# MOTOR_MAQUINA.net
KiCad netlist of a schematic drawn in Altium Designer
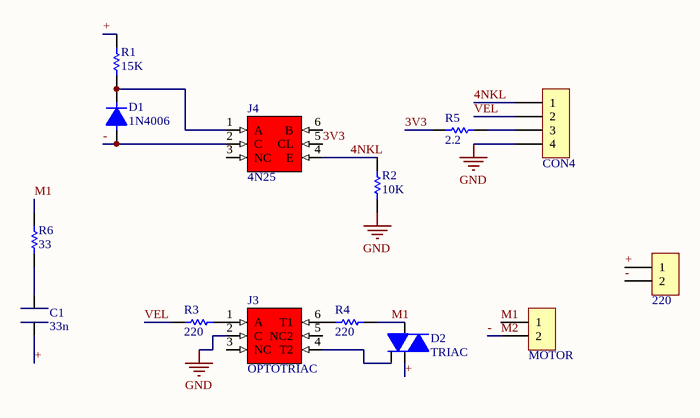
[diagram p0: MOTOR_MAQUINA.SchDoc]

(export (version "E")
  (design (tool "Eeschema 10.0.6"))
  (components
    (comp (ref "C1")
      (value "33n")
      (footprint "CAP300")
      (fields (field (name "AUTOR") "Brula, Tomas"))
      (libsource (lib "5A_BRULA,Tomas") (part "CAP"))
    )
    (comp (ref "D1") (value "1N4006") (footprint "DO41") (libsource (lib "5A_BRULA,Tomas") (part "DIODO")))
    (comp (ref "D2") (value "TRIAC") (footprint "TO-220 V") (libsource (lib "5A_BRULA,Tomas") (part "TRIAC")))
    (comp (ref "J1")
      (value "MOTOR")
      (footprint "BORNERA2")
      (libsource (lib "5A_BRULA,Tomas") (part "BORNERA 2"))
    )
    (comp (ref "J2")
      (value "220")
      (footprint "BORNERA2")
      (libsource (lib "5A_BRULA,Tomas") (part "BORNERA 2"))
    )
    (comp (ref "J3")
      (value "OPTOTRIAC")
      (footprint "DIP6")
      (libsource (lib "5A_BRULA,Tomas") (part "OPTOTRIAC"))
    )
    (comp (ref "J4") (value "4N25") (footprint "DIP6") (libsource (lib "5A_BRULA,Tomas") (part "4N25")))
    (comp (ref "J5") (value "CON4") (footprint "SIP4") (libsource (lib "5A_BRULA,Tomas") (part "CON4")))
    (comp (ref "R1") (value "15K") (footprint "R Axial 0.8") (libsource (lib "5A_BRULA,Tomas") (part "RES")))
    (comp (ref "R2") (value "10K") (footprint "0805") (libsource (lib "5A_BRULA,Tomas") (part "RES")))
    (comp (ref "R3") (value "220") (footprint "0805") (libsource (lib "5A_BRULA,Tomas") (part "RES")))
    (comp (ref "R4") (value "220") (footprint "0805") (libsource (lib "5A_BRULA,Tomas") (part "RES")))
    (comp (ref "R5") (value "2.2") (footprint "0805") (libsource (lib "LIBEBAL") (part "RES")))
    (comp (ref "R6") (value "33") (footprint "R Axial 0.8") (libsource (lib "5A_BRULA,Tomas") (part "RES")))
  )
  (nets
    (net (code "1") (name "/+") (class "Default")
      (node (ref "C1") (pin "2") (pinfunction "2_2") (pintype "passive"))
      (node (ref "D2") (pin "1") (pinfunction "1_1") (pintype "passive"))
      (node (ref "J2") (pin "1") (pinfunction "1_1") (pintype "passive"))
      (node (ref "R1") (pin "1") (pinfunction "1_1") (pintype "passive"))
    )
    (net (code "2") (name "/-") (class "Default")
      (node (ref "D1") (pin "1") (pinfunction "1_1") (pintype "passive"))
      (node (ref "J1") (pin "2") (pinfunction "2_2") (pintype "passive"))
      (node (ref "J2") (pin "2") (pinfunction "2_2") (pintype "passive"))
      (node (ref "J4") (pin "2") (pinfunction "C_2") (pintype "input"))
    )
    (net (code "3") (name "/3V3") (class "Default")
      (node (ref "J4") (pin "5") (pinfunction "CL_5") (pintype "input"))
      (node (ref "R5") (pin "2") (pinfunction "2_2") (pintype "passive"))
    )
    (net (code "4") (name "/4NKL") (class "Default")
      (node (ref "J4") (pin "4") (pinfunction "E_4") (pintype "input"))
      (node (ref "J5") (pin "1") (pinfunction "1_1") (pintype "passive"))
      (node (ref "R2") (pin "2") (pinfunction "2_2") (pintype "passive"))
    )
    (net (code "5") (name "/M1") (class "Default")
      (node (ref "D2") (pin "2") (pinfunction "2_2") (pintype "passive"))
      (node (ref "J1") (pin "1") (pinfunction "1_1") (pintype "passive"))
      (node (ref "R4") (pin "1") (pinfunction "1_1") (pintype "passive"))
      (node (ref "R6") (pin "2") (pinfunction "2_2") (pintype "passive"))
    )
    (net (code "6") (name "/VEL") (class "Default")
      (node (ref "J5") (pin "2") (pinfunction "2_2") (pintype "passive"))
      (node (ref "R3") (pin "2") (pinfunction "2_2") (pintype "passive"))
    )
    (net (code "7") (name "GND") (class "Default")
      (node (ref "J3") (pin "2") (pinfunction "C_2") (pintype "input"))
      (node (ref "J5") (pin "4") (pinfunction "4_4") (pintype "passive"))
      (node (ref "R2") (pin "1") (pinfunction "1_1") (pintype "passive"))
    )
    (net (code "8") (name "Net-(C1-Pad1)") (class "Default")
      (node (ref "C1") (pin "1") (pinfunction "1_1") (pintype "passive"))
      (node (ref "R6") (pin "1") (pinfunction "1_1") (pintype "passive"))
    )
    (net (code "9") (name "Net-(J3-A)") (class "Default")
      (node (ref "J3") (pin "1") (pinfunction "A_1") (pintype "input"))
      (node (ref "R3") (pin "1") (pinfunction "1_1") (pintype "passive"))
    )
    (net (code "10") (name "Net-(J3-T1)") (class "Default")
      (node (ref "J3") (pin "6") (pinfunction "T1_6") (pintype "input"))
      (node (ref "R4") (pin "2") (pinfunction "2_2") (pintype "passive"))
    )
    (net (code "11") (name "Net-(J3-T2)") (class "Default")
      (node (ref "D2") (pin "3") (pinfunction "3_3") (pintype "passive"))
      (node (ref "J3") (pin "4") (pinfunction "T2_4") (pintype "input"))
    )
    (net (code "12") (name "Net-(J4-A)") (class "Default")
      (node (ref "D1") (pin "2") (pinfunction "2_2") (pintype "passive"))
      (node (ref "J4") (pin "1") (pinfunction "A_1") (pintype "input"))
      (node (ref "R1") (pin "2") (pinfunction "2_2") (pintype "passive"))
    )
    (net (code "13") (name "Net-(J5-Pad3)") (class "Default")
      (node (ref "J5") (pin "3") (pinfunction "3_3") (pintype "passive"))
      (node (ref "R5") (pin "1") (pinfunction "1_1") (pintype "passive"))
    )
    (net (code "14") (name "unconnected-(J3-NC-Pad3)") (class "Default")
      (node (ref "J3") (pin "3") (pinfunction "NC_3") (pintype "input"))
    )
    (net (code "15") (name "unconnected-(J3-NC2-Pad5)") (class "Default")
      (node (ref "J3") (pin "5") (pinfunction "NC2_5") (pintype "input"))
    )
    (net (code "16") (name "unconnected-(J4-B-Pad6)") (class "Default")
      (node (ref "J4") (pin "6") (pinfunction "B_6") (pintype "input"))
    )
    (net (code "17") (name "unconnected-(J4-NC-Pad3)") (class "Default")
      (node (ref "J4") (pin "3") (pinfunction "NC_3") (pintype "input"))
    )
  )
)
